# Balancing_FETs.net
KiCad netlist of a schematic drawn in Altium Designer
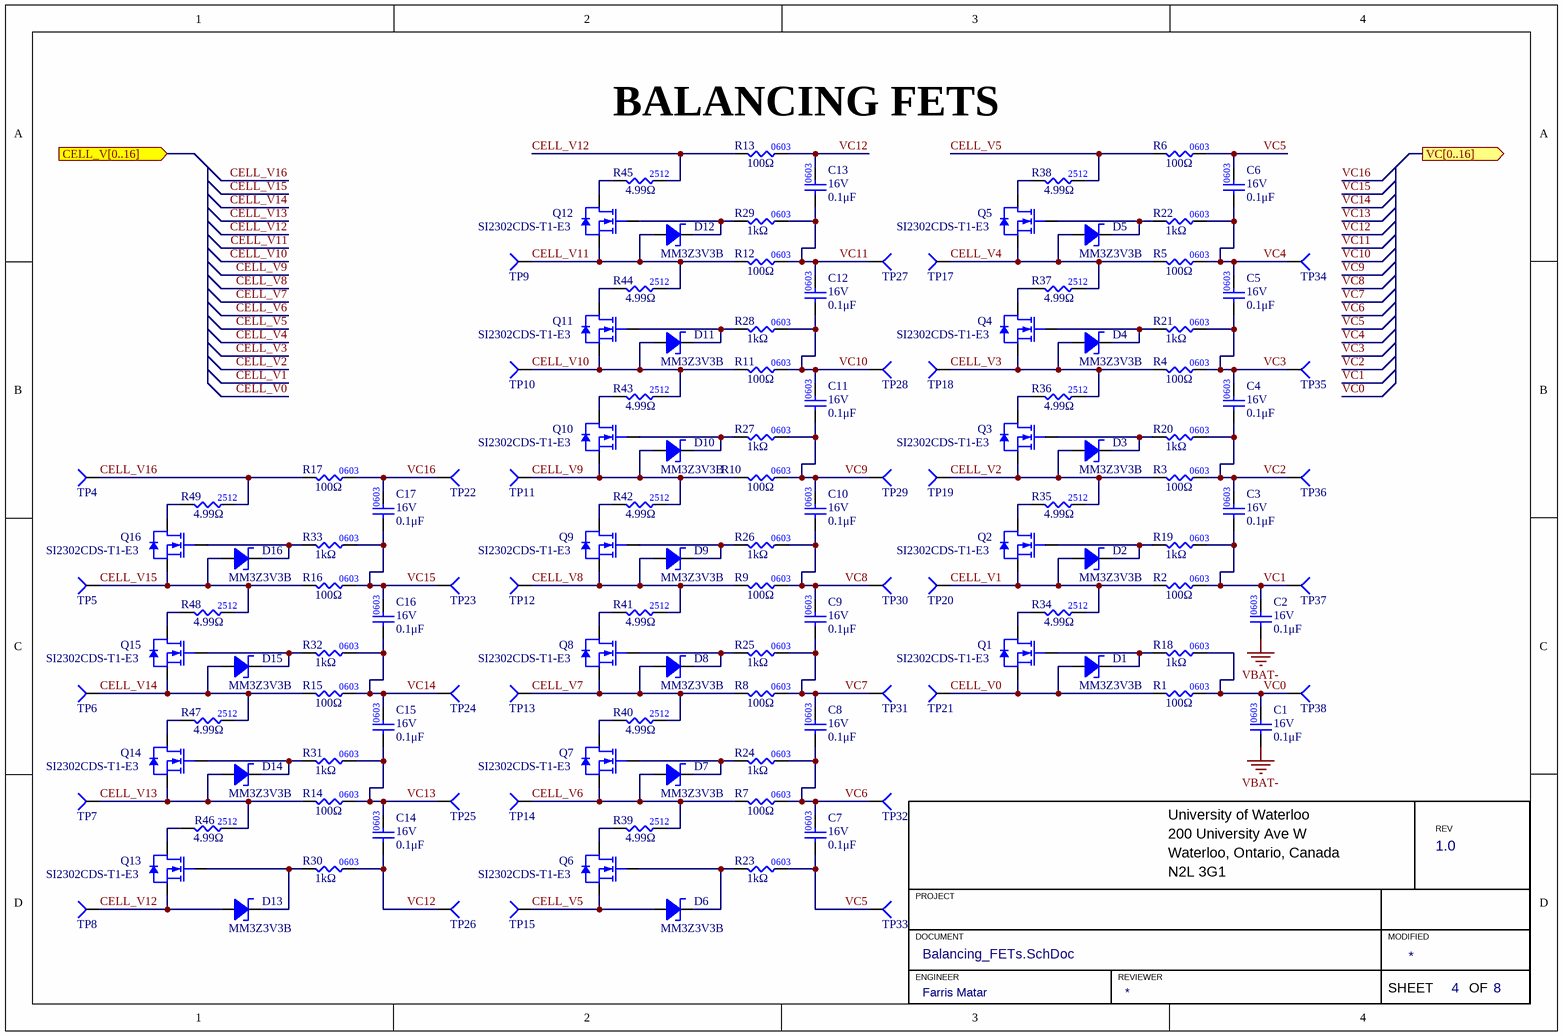
[diagram p0: Balancing_FETs.SchDoc]

(export (version "E")
  (design (tool "Eeschema 10.0.6"))
  (components
    (comp (ref "C1")
      (value "0.1μF")
      (footprint "CAP0603")
      (description "CAP CER 0.1UF 16V X7R 0603")
      (fields (field (name "VOLTAGE RATING") "16V") (field (name "Comment") "CAP_0.1uF_16V_0603"))
      (libsource (lib "Personal_Schematic_Library_2022") (part "CAP_0.1uF_16V_0603"))
    )
    (comp (ref "C2")
      (value "0.1μF")
      (footprint "CAP0603")
      (description "CAP CER 0.1UF 16V X7R 0603")
      (fields (field (name "VOLTAGE RATING") "16V") (field (name "Comment") "CAP_0.1uF_16V_0603"))
      (libsource (lib "Personal_Schematic_Library_2022") (part "CAP_0.1uF_16V_0603"))
    )
    (comp (ref "C3")
      (value "0.1μF")
      (footprint "CAP0603")
      (description "CAP CER 0.1UF 16V X7R 0603")
      (fields (field (name "VOLTAGE RATING") "16V") (field (name "Comment") "CAP_0.1uF_16V_0603"))
      (libsource (lib "Personal_Schematic_Library_2022") (part "CAP_0.1uF_16V_0603"))
    )
    (comp (ref "C4")
      (value "0.1μF")
      (footprint "CAP0603")
      (description "CAP CER 0.1UF 16V X7R 0603")
      (fields (field (name "VOLTAGE RATING") "16V") (field (name "Comment") "CAP_0.1uF_16V_0603"))
      (libsource (lib "Personal_Schematic_Library_2022") (part "CAP_0.1uF_16V_0603"))
    )
    (comp (ref "C5")
      (value "0.1μF")
      (footprint "CAP0603")
      (description "CAP CER 0.1UF 16V X7R 0603")
      (fields (field (name "VOLTAGE RATING") "16V") (field (name "Comment") "CAP_0.1uF_16V_0603"))
      (libsource (lib "Personal_Schematic_Library_2022") (part "CAP_0.1uF_16V_0603"))
    )
    (comp (ref "C6")
      (value "0.1μF")
      (footprint "CAP0603")
      (description "CAP CER 0.1UF 16V X7R 0603")
      (fields (field (name "VOLTAGE RATING") "16V") (field (name "Comment") "CAP_0.1uF_16V_0603"))
      (libsource (lib "Personal_Schematic_Library_2022") (part "CAP_0.1uF_16V_0603"))
    )
    (comp (ref "C7")
      (value "0.1μF")
      (footprint "CAP0603")
      (description "CAP CER 0.1UF 16V X7R 0603")
      (fields (field (name "VOLTAGE RATING") "16V") (field (name "Comment") "CAP_0.1uF_16V_0603"))
      (libsource (lib "Personal_Schematic_Library_2022") (part "CAP_0.1uF_16V_0603"))
    )
    (comp (ref "C8")
      (value "0.1μF")
      (footprint "CAP0603")
      (description "CAP CER 0.1UF 16V X7R 0603")
      (fields (field (name "VOLTAGE RATING") "16V") (field (name "Comment") "CAP_0.1uF_16V_0603"))
      (libsource (lib "Personal_Schematic_Library_2022") (part "CAP_0.1uF_16V_0603"))
    )
    (comp (ref "C9")
      (value "0.1μF")
      (footprint "CAP0603")
      (description "CAP CER 0.1UF 16V X7R 0603")
      (fields (field (name "VOLTAGE RATING") "16V") (field (name "Comment") "CAP_0.1uF_16V_0603"))
      (libsource (lib "Personal_Schematic_Library_2022") (part "CAP_0.1uF_16V_0603"))
    )
    (comp (ref "C10")
      (value "0.1μF")
      (footprint "CAP0603")
      (description "CAP CER 0.1UF 16V X7R 0603")
      (fields (field (name "VOLTAGE RATING") "16V") (field (name "Comment") "CAP_0.1uF_16V_0603"))
      (libsource (lib "Personal_Schematic_Library_2022") (part "CAP_0.1uF_16V_0603"))
    )
    (comp (ref "C11")
      (value "0.1μF")
      (footprint "CAP0603")
      (description "CAP CER 0.1UF 16V X7R 0603")
      (fields (field (name "VOLTAGE RATING") "16V") (field (name "Comment") "CAP_0.1uF_16V_0603"))
      (libsource (lib "Personal_Schematic_Library_2022") (part "CAP_0.1uF_16V_0603"))
    )
    (comp (ref "C12")
      (value "0.1μF")
      (footprint "CAP0603")
      (description "CAP CER 0.1UF 16V X7R 0603")
      (fields (field (name "VOLTAGE RATING") "16V") (field (name "Comment") "CAP_0.1uF_16V_0603"))
      (libsource (lib "Personal_Schematic_Library_2022") (part "CAP_0.1uF_16V_0603"))
    )
    (comp (ref "C13")
      (value "0.1μF")
      (footprint "CAP0603")
      (description "CAP CER 0.1UF 16V X7R 0603")
      (fields (field (name "VOLTAGE RATING") "16V") (field (name "Comment") "CAP_0.1uF_16V_0603"))
      (libsource (lib "Personal_Schematic_Library_2022") (part "CAP_0.1uF_16V_0603"))
    )
    (comp (ref "C14")
      (value "0.1μF")
      (footprint "CAP0603")
      (description "CAP CER 0.1UF 16V X7R 0603")
      (fields (field (name "VOLTAGE RATING") "16V") (field (name "Comment") "CAP_0.1uF_16V_0603"))
      (libsource (lib "Personal_Schematic_Library_2022") (part "CAP_0.1uF_16V_0603"))
    )
    (comp (ref "C15")
      (value "0.1μF")
      (footprint "CAP0603")
      (description "CAP CER 0.1UF 16V X7R 0603")
      (fields (field (name "VOLTAGE RATING") "16V") (field (name "Comment") "CAP_0.1uF_16V_0603"))
      (libsource (lib "Personal_Schematic_Library_2022") (part "CAP_0.1uF_16V_0603"))
    )
    (comp (ref "C16")
      (value "0.1μF")
      (footprint "CAP0603")
      (description "CAP CER 0.1UF 16V X7R 0603")
      (fields (field (name "VOLTAGE RATING") "16V") (field (name "Comment") "CAP_0.1uF_16V_0603"))
      (libsource (lib "Personal_Schematic_Library_2022") (part "CAP_0.1uF_16V_0603"))
    )
    (comp (ref "C17")
      (value "0.1μF")
      (footprint "CAP0603")
      (description "CAP CER 0.1UF 16V X7R 0603")
      (fields (field (name "VOLTAGE RATING") "16V") (field (name "Comment") "CAP_0.1uF_16V_0603"))
      (libsource (lib "Personal_Schematic_Library_2022") (part "CAP_0.1uF_16V_0603"))
    )
    (comp (ref "D1")
      (value "DIO_ZENER_3V3")
      (footprint "DIO_ZENER_3V3")
      (description "DIODE ZENER 3.3V 200mW SOD323F")
      (fields (field (name "MANUFACTURER PART NUMBER 1") "MM3Z3V3B"))
      (libsource (lib "Personal_Schematic_Library_2022") (part "DIO_ZENER_3V3"))
    )
    (comp (ref "D2")
      (value "DIO_ZENER_3V3")
      (footprint "DIO_ZENER_3V3")
      (description "DIODE ZENER 3.3V 200mW SOD323F")
      (fields (field (name "MANUFACTURER PART NUMBER 1") "MM3Z3V3B"))
      (libsource (lib "Personal_Schematic_Library_2022") (part "DIO_ZENER_3V3"))
    )
    (comp (ref "D3")
      (value "DIO_ZENER_3V3")
      (footprint "DIO_ZENER_3V3")
      (description "DIODE ZENER 3.3V 200mW SOD323F")
      (fields (field (name "MANUFACTURER PART NUMBER 1") "MM3Z3V3B"))
      (libsource (lib "Personal_Schematic_Library_2022") (part "DIO_ZENER_3V3"))
    )
    (comp (ref "D4")
      (value "DIO_ZENER_3V3")
      (footprint "DIO_ZENER_3V3")
      (description "DIODE ZENER 3.3V 200mW SOD323F")
      (fields (field (name "MANUFACTURER PART NUMBER 1") "MM3Z3V3B"))
      (libsource (lib "Personal_Schematic_Library_2022") (part "DIO_ZENER_3V3"))
    )
    (comp (ref "D5")
      (value "DIO_ZENER_3V3")
      (footprint "DIO_ZENER_3V3")
      (description "DIODE ZENER 3.3V 200mW SOD323F")
      (fields (field (name "MANUFACTURER PART NUMBER 1") "MM3Z3V3B"))
      (libsource (lib "Personal_Schematic_Library_2022") (part "DIO_ZENER_3V3"))
    )
    (comp (ref "D6")
      (value "DIO_ZENER_3V3")
      (footprint "DIO_ZENER_3V3")
      (description "DIODE ZENER 3.3V 200mW SOD323F")
      (fields (field (name "MANUFACTURER PART NUMBER 1") "MM3Z3V3B"))
      (libsource (lib "Personal_Schematic_Library_2022") (part "DIO_ZENER_3V3"))
    )
    (comp (ref "D7")
      (value "DIO_ZENER_3V3")
      (footprint "DIO_ZENER_3V3")
      (description "DIODE ZENER 3.3V 200mW SOD323F")
      (fields (field (name "MANUFACTURER PART NUMBER 1") "MM3Z3V3B"))
      (libsource (lib "Personal_Schematic_Library_2022") (part "DIO_ZENER_3V3"))
    )
    (comp (ref "D8")
      (value "DIO_ZENER_3V3")
      (footprint "DIO_ZENER_3V3")
      (description "DIODE ZENER 3.3V 200mW SOD323F")
      (fields (field (name "MANUFACTURER PART NUMBER 1") "MM3Z3V3B"))
      (libsource (lib "Personal_Schematic_Library_2022") (part "DIO_ZENER_3V3"))
    )
    (comp (ref "D9")
      (value "DIO_ZENER_3V3")
      (footprint "DIO_ZENER_3V3")
      (description "DIODE ZENER 3.3V 200mW SOD323F")
      (fields (field (name "MANUFACTURER PART NUMBER 1") "MM3Z3V3B"))
      (libsource (lib "Personal_Schematic_Library_2022") (part "DIO_ZENER_3V3"))
    )
    (comp (ref "D10")
      (value "DIO_ZENER_3V3")
      (footprint "DIO_ZENER_3V3")
      (description "DIODE ZENER 3.3V 200mW SOD323F")
      (fields (field (name "MANUFACTURER PART NUMBER 1") "MM3Z3V3B"))
      (libsource (lib "Personal_Schematic_Library_2022") (part "DIO_ZENER_3V3"))
    )
    (comp (ref "D11")
      (value "DIO_ZENER_3V3")
      (footprint "DIO_ZENER_3V3")
      (description "DIODE ZENER 3.3V 200mW SOD323F")
      (fields (field (name "MANUFACTURER PART NUMBER 1") "MM3Z3V3B"))
      (libsource (lib "Personal_Schematic_Library_2022") (part "DIO_ZENER_3V3"))
    )
    (comp (ref "D12")
      (value "DIO_ZENER_3V3")
      (footprint "DIO_ZENER_3V3")
      (description "DIODE ZENER 3.3V 200mW SOD323F")
      (fields (field (name "MANUFACTURER PART NUMBER 1") "MM3Z3V3B"))
      (libsource (lib "Personal_Schematic_Library_2022") (part "DIO_ZENER_3V3"))
    )
    (comp (ref "D13")
      (value "DIO_ZENER_3V3")
      (footprint "DIO_ZENER_3V3")
      (description "DIODE ZENER 3.3V 200mW SOD323F")
      (fields (field (name "MANUFACTURER PART NUMBER 1") "MM3Z3V3B"))
      (libsource (lib "Personal_Schematic_Library_2022") (part "DIO_ZENER_3V3"))
    )
    (comp (ref "D14")
      (value "DIO_ZENER_3V3")
      (footprint "DIO_ZENER_3V3")
      (description "DIODE ZENER 3.3V 200mW SOD323F")
      (fields (field (name "MANUFACTURER PART NUMBER 1") "MM3Z3V3B"))
      (libsource (lib "Personal_Schematic_Library_2022") (part "DIO_ZENER_3V3"))
    )
    (comp (ref "D15")
      (value "DIO_ZENER_3V3")
      (footprint "DIO_ZENER_3V3")
      (description "DIODE ZENER 3.3V 200mW SOD323F")
      (fields (field (name "MANUFACTURER PART NUMBER 1") "MM3Z3V3B"))
      (libsource (lib "Personal_Schematic_Library_2022") (part "DIO_ZENER_3V3"))
    )
    (comp (ref "D16")
      (value "DIO_ZENER_3V3")
      (footprint "DIO_ZENER_3V3")
      (description "DIODE ZENER 3.3V 200mW SOD323F")
      (fields (field (name "MANUFACTURER PART NUMBER 1") "MM3Z3V3B"))
      (libsource (lib "Personal_Schematic_Library_2022") (part "DIO_ZENER_3V3"))
    )
    (comp (ref "Q1")
      (value "NMOS_20V_6A")
      (footprint "SOT23-3")
      (description "MOSFET N-CH 20V 2.6A SOT23-3")
      (fields (field (name "MANUFACTURER PART NUMBER 1") "SI2302CDS-T1-E3"))
      (libsource (lib "Personal_Schematic_Library_2022") (part "NMOS_20V_2.6A"))
    )
    (comp (ref "Q2")
      (value "NMOS_20V_6A")
      (footprint "SOT23-3")
      (description "MOSFET N-CH 20V 2.6A SOT23-3")
      (fields (field (name "MANUFACTURER PART NUMBER 1") "SI2302CDS-T1-E3"))
      (libsource (lib "Personal_Schematic_Library_2022") (part "NMOS_20V_2.6A"))
    )
    (comp (ref "Q3")
      (value "NMOS_20V_6A")
      (footprint "SOT23-3")
      (description "MOSFET N-CH 20V 2.6A SOT23-3")
      (fields (field (name "MANUFACTURER PART NUMBER 1") "SI2302CDS-T1-E3"))
      (libsource (lib "Personal_Schematic_Library_2022") (part "NMOS_20V_2.6A"))
    )
    (comp (ref "Q4")
      (value "NMOS_20V_6A")
      (footprint "SOT23-3")
      (description "MOSFET N-CH 20V 2.6A SOT23-3")
      (fields (field (name "MANUFACTURER PART NUMBER 1") "SI2302CDS-T1-E3"))
      (libsource (lib "Personal_Schematic_Library_2022") (part "NMOS_20V_2.6A"))
    )
    (comp (ref "Q5")
      (value "NMOS_20V_6A")
      (footprint "SOT23-3")
      (description "MOSFET N-CH 20V 2.6A SOT23-3")
      (fields (field (name "MANUFACTURER PART NUMBER 1") "SI2302CDS-T1-E3"))
      (libsource (lib "Personal_Schematic_Library_2022") (part "NMOS_20V_2.6A"))
    )
    (comp (ref "Q6")
      (value "NMOS_20V_6A")
      (footprint "SOT23-3")
      (description "MOSFET N-CH 20V 2.6A SOT23-3")
      (fields (field (name "MANUFACTURER PART NUMBER 1") "SI2302CDS-T1-E3"))
      (libsource (lib "Personal_Schematic_Library_2022") (part "NMOS_20V_2.6A"))
    )
    (comp (ref "Q7")
      (value "NMOS_20V_6A")
      (footprint "SOT23-3")
      (description "MOSFET N-CH 20V 2.6A SOT23-3")
      (fields (field (name "MANUFACTURER PART NUMBER 1") "SI2302CDS-T1-E3"))
      (libsource (lib "Personal_Schematic_Library_2022") (part "NMOS_20V_2.6A"))
    )
    (comp (ref "Q8")
      (value "NMOS_20V_6A")
      (footprint "SOT23-3")
      (description "MOSFET N-CH 20V 2.6A SOT23-3")
      (fields (field (name "MANUFACTURER PART NUMBER 1") "SI2302CDS-T1-E3"))
      (libsource (lib "Personal_Schematic_Library_2022") (part "NMOS_20V_2.6A"))
    )
    (comp (ref "Q9")
      (value "NMOS_20V_6A")
      (footprint "SOT23-3")
      (description "MOSFET N-CH 20V 2.6A SOT23-3")
      (fields (field (name "MANUFACTURER PART NUMBER 1") "SI2302CDS-T1-E3"))
      (libsource (lib "Personal_Schematic_Library_2022") (part "NMOS_20V_2.6A"))
    )
    (comp (ref "Q10")
      (value "NMOS_20V_6A")
      (footprint "SOT23-3")
      (description "MOSFET N-CH 20V 2.6A SOT23-3")
      (fields (field (name "MANUFACTURER PART NUMBER 1") "SI2302CDS-T1-E3"))
      (libsource (lib "Personal_Schematic_Library_2022") (part "NMOS_20V_2.6A"))
    )
    (comp (ref "Q11")
      (value "NMOS_20V_6A")
      (footprint "SOT23-3")
      (description "MOSFET N-CH 20V 2.6A SOT23-3")
      (fields (field (name "MANUFACTURER PART NUMBER 1") "SI2302CDS-T1-E3"))
      (libsource (lib "Personal_Schematic_Library_2022") (part "NMOS_20V_2.6A"))
    )
    (comp (ref "Q12")
      (value "NMOS_20V_6A")
      (footprint "SOT23-3")
      (description "MOSFET N-CH 20V 2.6A SOT23-3")
      (fields (field (name "MANUFACTURER PART NUMBER 1") "SI2302CDS-T1-E3"))
      (libsource (lib "Personal_Schematic_Library_2022") (part "NMOS_20V_2.6A"))
    )
    (comp (ref "Q13")
      (value "NMOS_20V_6A")
      (footprint "SOT23-3")
      (description "MOSFET N-CH 20V 2.6A SOT23-3")
      (fields (field (name "MANUFACTURER PART NUMBER 1") "SI2302CDS-T1-E3"))
      (libsource (lib "Personal_Schematic_Library_2022") (part "NMOS_20V_2.6A"))
    )
    (comp (ref "Q14")
      (value "NMOS_20V_6A")
      (footprint "SOT23-3")
      (description "MOSFET N-CH 20V 2.6A SOT23-3")
      (fields (field (name "MANUFACTURER PART NUMBER 1") "SI2302CDS-T1-E3"))
      (libsource (lib "Personal_Schematic_Library_2022") (part "NMOS_20V_2.6A"))
    )
    (comp (ref "Q15")
      (value "NMOS_20V_6A")
      (footprint "SOT23-3")
      (description "MOSFET N-CH 20V 2.6A SOT23-3")
      (fields (field (name "MANUFACTURER PART NUMBER 1") "SI2302CDS-T1-E3"))
      (libsource (lib "Personal_Schematic_Library_2022") (part "NMOS_20V_2.6A"))
    )
    (comp (ref "Q16")
      (value "NMOS_20V_6A")
      (footprint "SOT23-3")
      (description "MOSFET N-CH 20V 2.6A SOT23-3")
      (fields (field (name "MANUFACTURER PART NUMBER 1") "SI2302CDS-T1-E3"))
      (libsource (lib "Personal_Schematic_Library_2022") (part "NMOS_20V_2.6A"))
    )
    (comp (ref "R1")
      (value "100Ω")
      (footprint "RES0603")
      (description "RES 100 OHM 1% 1/10W 0603")
      (fields (field (name "Comment") "RES_100Ω_0603_1%"))
      (libsource (lib "Personal_Schematic_Library_2022") (part "RES_100Ω_0603_1%"))
    )
    (comp (ref "R2")
      (value "100Ω")
      (footprint "RES0603")
      (description "RES 100 OHM 1% 1/10W 0603")
      (fields (field (name "Comment") "RES_100Ω_0603_1%"))
      (libsource (lib "Personal_Schematic_Library_2022") (part "RES_100Ω_0603_1%"))
    )
    (comp (ref "R3")
      (value "100Ω")
      (footprint "RES0603")
      (description "RES 100 OHM 1% 1/10W 0603")
      (fields (field (name "Comment") "RES_100Ω_0603_1%"))
      (libsource (lib "Personal_Schematic_Library_2022") (part "RES_100Ω_0603_1%"))
    )
    (comp (ref "R4")
      (value "100Ω")
      (footprint "RES0603")
      (description "RES 100 OHM 1% 1/10W 0603")
      (fields (field (name "Comment") "RES_100Ω_0603_1%"))
      (libsource (lib "Personal_Schematic_Library_2022") (part "RES_100Ω_0603_1%"))
    )
    (comp (ref "R5")
      (value "100Ω")
      (footprint "RES0603")
      (description "RES 100 OHM 1% 1/10W 0603")
      (fields (field (name "Comment") "RES_100Ω_0603_1%"))
      (libsource (lib "Personal_Schematic_Library_2022") (part "RES_100Ω_0603_1%"))
    )
    (comp (ref "R6")
      (value "100Ω")
      (footprint "RES0603")
      (description "RES 100 OHM 1% 1/10W 0603")
      (fields (field (name "Comment") "RES_100Ω_0603_1%"))
      (libsource (lib "Personal_Schematic_Library_2022") (part "RES_100Ω_0603_1%"))
    )
    (comp (ref "R7")
      (value "100Ω")
      (footprint "RES0603")
      (description "RES 100 OHM 1% 1/10W 0603")
      (fields (field (name "Comment") "RES_100Ω_0603_1%"))
      (libsource (lib "Personal_Schematic_Library_2022") (part "RES_100Ω_0603_1%"))
    )
    (comp (ref "R8")
      (value "100Ω")
      (footprint "RES0603")
      (description "RES 100 OHM 1% 1/10W 0603")
      (fields (field (name "Comment") "RES_100Ω_0603_1%"))
      (libsource (lib "Personal_Schematic_Library_2022") (part "RES_100Ω_0603_1%"))
    )
    (comp (ref "R9")
      (value "100Ω")
      (footprint "RES0603")
      (description "RES 100 OHM 1% 1/10W 0603")
      (fields (field (name "Comment") "RES_100Ω_0603_1%"))
      (libsource (lib "Personal_Schematic_Library_2022") (part "RES_100Ω_0603_1%"))
    )
    (comp (ref "R10")
      (value "100Ω")
      (footprint "RES0603")
      (description "RES 100 OHM 1% 1/10W 0603")
      (fields (field (name "Comment") "RES_100Ω_0603_1%"))
      (libsource (lib "Personal_Schematic_Library_2022") (part "RES_100Ω_0603_1%"))
    )
    (comp (ref "R11")
      (value "100Ω")
      (footprint "RES0603")
      (description "RES 100 OHM 1% 1/10W 0603")
      (fields (field (name "Comment") "RES_100Ω_0603_1%"))
      (libsource (lib "Personal_Schematic_Library_2022") (part "RES_100Ω_0603_1%"))
    )
    (comp (ref "R12")
      (value "100Ω")
      (footprint "RES0603")
      (description "RES 100 OHM 1% 1/10W 0603")
      (fields (field (name "Comment") "RES_100Ω_0603_1%"))
      (libsource (lib "Personal_Schematic_Library_2022") (part "RES_100Ω_0603_1%"))
    )
    (comp (ref "R13")
      (value "100Ω")
      (footprint "RES0603")
      (description "RES 100 OHM 1% 1/10W 0603")
      (fields (field (name "Comment") "RES_100Ω_0603_1%"))
      (libsource (lib "Personal_Schematic_Library_2022") (part "RES_100Ω_0603_1%"))
    )
    (comp (ref "R14")
      (value "100Ω")
      (footprint "RES0603")
      (description "RES 100 OHM 1% 1/10W 0603")
      (fields (field (name "Comment") "RES_100Ω_0603_1%"))
      (libsource (lib "Personal_Schematic_Library_2022") (part "RES_100Ω_0603_1%"))
    )
    (comp (ref "R15")
      (value "100Ω")
      (footprint "RES0603")
      (description "RES 100 OHM 1% 1/10W 0603")
      (fields (field (name "Comment") "RES_100Ω_0603_1%"))
      (libsource (lib "Personal_Schematic_Library_2022") (part "RES_100Ω_0603_1%"))
    )
    (comp (ref "R16")
      (value "100Ω")
      (footprint "RES0603")
      (description "RES 100 OHM 1% 1/10W 0603")
      (fields (field (name "Comment") "RES_100Ω_0603_1%"))
      (libsource (lib "Personal_Schematic_Library_2022") (part "RES_100Ω_0603_1%"))
    )
    (comp (ref "R17")
      (value "100Ω")
      (footprint "RES0603")
      (description "RES 100 OHM 1% 1/10W 0603")
      (fields (field (name "Comment") "RES_100Ω_0603_1%"))
      (libsource (lib "Personal_Schematic_Library_2022") (part "RES_100Ω_0603_1%"))
    )
    (comp (ref "R18")
      (value "1kΩ")
      (footprint "RES0603")
      (description "RES 1K OHM 1% 1/8W 0603")
      (fields (field (name "Comment") "RES_1kΩ_0603_1%"))
      (libsource (lib "Personal_Schematic_Library_2022") (part "RES_1kΩ_0603_1%"))
    )
    (comp (ref "R19")
      (value "1kΩ")
      (footprint "RES0603")
      (description "RES 1K OHM 1% 1/8W 0603")
      (fields (field (name "Comment") "RES_1kΩ_0603_1%"))
      (libsource (lib "Personal_Schematic_Library_2022") (part "RES_1kΩ_0603_1%"))
    )
    (comp (ref "R20")
      (value "1kΩ")
      (footprint "RES0603")
      (description "RES 1K OHM 1% 1/8W 0603")
      (fields (field (name "Comment") "RES_1kΩ_0603_1%"))
      (libsource (lib "Personal_Schematic_Library_2022") (part "RES_1kΩ_0603_1%"))
    )
    (comp (ref "R21")
      (value "1kΩ")
      (footprint "RES0603")
      (description "RES 1K OHM 1% 1/8W 0603")
      (fields (field (name "Comment") "RES_1kΩ_0603_1%"))
      (libsource (lib "Personal_Schematic_Library_2022") (part "RES_1kΩ_0603_1%"))
    )
    (comp (ref "R22")
      (value "1kΩ")
      (footprint "RES0603")
      (description "RES 1K OHM 1% 1/8W 0603")
      (fields (field (name "Comment") "RES_1kΩ_0603_1%"))
      (libsource (lib "Personal_Schematic_Library_2022") (part "RES_1kΩ_0603_1%"))
    )
    (comp (ref "R23")
      (value "1kΩ")
      (footprint "RES0603")
      (description "RES 1K OHM 1% 1/8W 0603")
      (fields (field (name "Comment") "RES_1kΩ_0603_1%"))
      (libsource (lib "Personal_Schematic_Library_2022") (part "RES_1kΩ_0603_1%"))
    )
    (comp (ref "R24")
      (value "1kΩ")
      (footprint "RES0603")
      (description "RES 1K OHM 1% 1/8W 0603")
      (fields (field (name "Comment") "RES_1kΩ_0603_1%"))
      (libsource (lib "Personal_Schematic_Library_2022") (part "RES_1kΩ_0603_1%"))
    )
    (comp (ref "R25")
      (value "1kΩ")
      (footprint "RES0603")
      (description "RES 1K OHM 1% 1/8W 0603")
      (fields (field (name "Comment") "RES_1kΩ_0603_1%"))
      (libsource (lib "Personal_Schematic_Library_2022") (part "RES_1kΩ_0603_1%"))
    )
    (comp (ref "R26")
      (value "1kΩ")
      (footprint "RES0603")
      (description "RES 1K OHM 1% 1/8W 0603")
      (fields (field (name "Comment") "RES_1kΩ_0603_1%"))
      (libsource (lib "Personal_Schematic_Library_2022") (part "RES_1kΩ_0603_1%"))
    )
    (comp (ref "R27")
      (value "1kΩ")
      (footprint "RES0603")
      (description "RES 1K OHM 1% 1/8W 0603")
      (fields (field (name "Comment") "RES_1kΩ_0603_1%"))
      (libsource (lib "Personal_Schematic_Library_2022") (part "RES_1kΩ_0603_1%"))
    )
    (comp (ref "R28")
      (value "1kΩ")
      (footprint "RES0603")
      (description "RES 1K OHM 1% 1/8W 0603")
      (fields (field (name "Comment") "RES_1kΩ_0603_1%"))
      (libsource (lib "Personal_Schematic_Library_2022") (part "RES_1kΩ_0603_1%"))
    )
    (comp (ref "R29")
      (value "1kΩ")
      (footprint "RES0603")
      (description "RES 1K OHM 1% 1/8W 0603")
      (fields (field (name "Comment") "RES_1kΩ_0603_1%"))
      (libsource (lib "Personal_Schematic_Library_2022") (part "RES_1kΩ_0603_1%"))
    )
    (comp (ref "R30")
      (value "1kΩ")
      (footprint "RES0603")
      (description "RES 1K OHM 1% 1/8W 0603")
      (fields (field (name "Comment") "RES_1kΩ_0603_1%"))
      (libsource (lib "Personal_Schematic_Library_2022") (part "RES_1kΩ_0603_1%"))
    )
    (comp (ref "R31")
      (value "1kΩ")
      (footprint "RES0603")
      (description "RES 1K OHM 1% 1/8W 0603")
      (fields (field (name "Comment") "RES_1kΩ_0603_1%"))
      (libsource (lib "Personal_Schematic_Library_2022") (part "RES_1kΩ_0603_1%"))
    )
    (comp (ref "R32")
      (value "1kΩ")
      (footprint "RES0603")
      (description "RES 1K OHM 1% 1/8W 0603")
      (fields (field (name "Comment") "RES_1kΩ_0603_1%"))
      (libsource (lib "Personal_Schematic_Library_2022") (part "RES_1kΩ_0603_1%"))
    )
    (comp (ref "R33")
      (value "1kΩ")
      (footprint "RES0603")
      (description "RES 1K OHM 1% 1/8W 0603")
      (fields (field (name "Comment") "RES_1kΩ_0603_1%"))
      (libsource (lib "Personal_Schematic_Library_2022") (part "RES_1kΩ_0603_1%"))
    )
    (comp (ref "R34")
      (value "4.99Ω")
      (footprint "RES2512")
      (description "RES 4.99 OHM 1% 2W 2512")
      (fields (field (name "Comment") "RES_4.99Ω_2512_1%"))
      (libsource (lib "Personal_Schematic_Library_2022") (part "RES_4.99Ω_2512_1%"))
    )
    (comp (ref "R35")
      (value "4.99Ω")
      (footprint "RES2512")
      (description "RES 4.99 OHM 1% 2W 2512")
      (fields (field (name "Comment") "RES_4.99Ω_2512_1%"))
      (libsource (lib "Personal_Schematic_Library_2022") (part "RES_4.99Ω_2512_1%"))
    )
    (comp (ref "R36")
      (value "4.99Ω")
      (footprint "RES2512")
      (description "RES 4.99 OHM 1% 2W 2512")
      (fields (field (name "Comment") "RES_4.99Ω_2512_1%"))
      (libsource (lib "Personal_Schematic_Library_2022") (part "RES_4.99Ω_2512_1%"))
    )
    (comp (ref "R37")
      (value "4.99Ω")
      (footprint "RES2512")
      (description "RES 4.99 OHM 1% 2W 2512")
      (fields (field (name "Comment") "RES_4.99Ω_2512_1%"))
      (libsource (lib "Personal_Schematic_Library_2022") (part "RES_4.99Ω_2512_1%"))
    )
    (comp (ref "R38")
      (value "4.99Ω")
      (footprint "RES2512")
      (description "RES 4.99 OHM 1% 2W 2512")
      (fields (field (name "Comment") "RES_4.99Ω_2512_1%"))
      (libsource (lib "Personal_Schematic_Library_2022") (part "RES_4.99Ω_2512_1%"))
    )
    (comp (ref "R39")
      (value "4.99Ω")
      (footprint "RES2512")
      (description "RES 4.99 OHM 1% 2W 2512")
      (fields (field (name "Comment") "RES_4.99Ω_2512_1%"))
      (libsource (lib "Personal_Schematic_Library_2022") (part "RES_4.99Ω_2512_1%"))
    )
    (comp (ref "R40")
      (value "4.99Ω")
      (footprint "RES2512")
      (description "RES 4.99 OHM 1% 2W 2512")
      (fields (field (name "Comment") "RES_4.99Ω_2512_1%"))
      (libsource (lib "Personal_Schematic_Library_2022") (part "RES_4.99Ω_2512_1%"))
    )
    (comp (ref "R41")
      (value "4.99Ω")
      (footprint "RES2512")
      (description "RES 4.99 OHM 1% 2W 2512")
      (fields (field (name "Comment") "RES_4.99Ω_2512_1%"))
      (libsource (lib "Personal_Schematic_Library_2022") (part "RES_4.99Ω_2512_1%"))
    )
    (comp (ref "R42")
      (value "4.99Ω")
      (footprint "RES2512")
      (description "RES 4.99 OHM 1% 2W 2512")
      (fields (field (name "Comment") "RES_4.99Ω_2512_1%"))
      (libsource (lib "Personal_Schematic_Library_2022") (part "RES_4.99Ω_2512_1%"))
    )
    (comp (ref "R43")
      (value "4.99Ω")
      (footprint "RES2512")
      (description "RES 4.99 OHM 1% 2W 2512")
      (fields (field (name "Comment") "RES_4.99Ω_2512_1%"))
      (libsource (lib "Personal_Schematic_Library_2022") (part "RES_4.99Ω_2512_1%"))
    )
    (comp (ref "R44")
      (value "4.99Ω")
      (footprint "RES2512")
      (description "RES 4.99 OHM 1% 2W 2512")
      (fields (field (name "Comment") "RES_4.99Ω_2512_1%"))
      (libsource (lib "Personal_Schematic_Library_2022") (part "RES_4.99Ω_2512_1%"))
    )
    (comp (ref "R45")
      (value "4.99Ω")
      (footprint "RES2512")
      (description "RES 4.99 OHM 1% 2W 2512")
      (fields (field (name "Comment") "RES_4.99Ω_2512_1%"))
      (libsource (lib "Personal_Schematic_Library_2022") (part "RES_4.99Ω_2512_1%"))
    )
    (comp (ref "R46")
      (value "4.99Ω")
      (footprint "RES2512")
      (description "RES 4.99 OHM 1% 2W 2512")
      (fields (field (name "Comment") "RES_4.99Ω_2512_1%"))
      (libsource (lib "Personal_Schematic_Library_2022") (part "RES_4.99Ω_2512_1%"))
    )
    (comp (ref "R47")
      (value "4.99Ω")
      (footprint "RES2512")
      (description "RES 4.99 OHM 1% 2W 2512")
      (fields (field (name "Comment") "RES_4.99Ω_2512_1%"))
      (libsource (lib "Personal_Schematic_Library_2022") (part "RES_4.99Ω_2512_1%"))
    )
    (comp (ref "R48")
      (value "4.99Ω")
      (footprint "RES2512")
      (description "RES 4.99 OHM 1% 2W 2512")
      (fields (field (name "Comment") "RES_4.99Ω_2512_1%"))
      (libsource (lib "Personal_Schematic_Library_2022") (part "RES_4.99Ω_2512_1%"))
    )
    (comp (ref "R49")
      (value "4.99Ω")
      (footprint "RES2512")
      (description "RES 4.99 OHM 1% 2W 2512")
      (fields (field (name "Comment") "RES_4.99Ω_2512_1%"))
      (libsource (lib "Personal_Schematic_Library_2022") (part "RES_4.99Ω_2512_1%"))
    )
    (comp (ref "TP4")
      (value "TESTPOINT_1MM_SQUARE")
      (footprint "TESTPOINT_SQUARE_1MM")
      (description "TESTPOINT 1MM SQUARE")
      (libsource (lib "Personal_Schematic_Library_2022") (part "TESTPOINT_1MM_SQUARE"))
    )
    (comp (ref "TP5")
      (value "TESTPOINT_1MM_SQUARE")
      (footprint "TESTPOINT_SQUARE_1MM")
      (description "TESTPOINT 1MM SQUARE")
      (libsource (lib "Personal_Schematic_Library_2022") (part "TESTPOINT_1MM_SQUARE"))
    )
    (comp (ref "TP6")
      (value "TESTPOINT_1MM_SQUARE")
      (footprint "TESTPOINT_SQUARE_1MM")
      (description "TESTPOINT 1MM SQUARE")
      (libsource (lib "Personal_Schematic_Library_2022") (part "TESTPOINT_1MM_SQUARE"))
    )
    (comp (ref "TP7")
      (value "TESTPOINT_1MM_SQUARE")
      (footprint "TESTPOINT_SQUARE_1MM")
      (description "TESTPOINT 1MM SQUARE")
      (libsource (lib "Personal_Schematic_Library_2022") (part "TESTPOINT_1MM_SQUARE"))
    )
    (comp (ref "TP8")
      (value "TESTPOINT_1MM_SQUARE")
      (footprint "TESTPOINT_SQUARE_1MM")
      (description "TESTPOINT 1MM SQUARE")
      (libsource (lib "Personal_Schematic_Library_2022") (part "TESTPOINT_1MM_SQUARE"))
    )
    (comp (ref "TP9")
      (value "TESTPOINT_1MM_SQUARE")
      (footprint "TESTPOINT_SQUARE_1MM")
      (description "TESTPOINT 1MM SQUARE")
      (libsource (lib "Personal_Schematic_Library_2022") (part "TESTPOINT_1MM_SQUARE"))
    )
    (comp (ref "TP10")
      (value "TESTPOINT_1MM_SQUARE")
      (footprint "TESTPOINT_SQUARE_1MM")
      (description "TESTPOINT 1MM SQUARE")
      (libsource (lib "Personal_Schematic_Library_2022") (part "TESTPOINT_1MM_SQUARE"))
    )
    (comp (ref "TP11")
      (value "TESTPOINT_1MM_SQUARE")
      (footprint "TESTPOINT_SQUARE_1MM")
      (description "TESTPOINT 1MM SQUARE")
      (libsource (lib "Personal_Schematic_Library_2022") (part "TESTPOINT_1MM_SQUARE"))
    )
    (comp (ref "TP12")
      (value "TESTPOINT_1MM_SQUARE")
      (footprint "TESTPOINT_SQUARE_1MM")
      (description "TESTPOINT 1MM SQUARE")
      (libsource (lib "Personal_Schematic_Library_2022") (part "TESTPOINT_1MM_SQUARE"))
    )
    (comp (ref "TP13")
      (value "TESTPOINT_1MM_SQUARE")
      (footprint "TESTPOINT_SQUARE_1MM")
      (description "TESTPOINT 1MM SQUARE")
      (libsource (lib "Personal_Schematic_Library_2022") (part "TESTPOINT_1MM_SQUARE"))
    )
    (comp (ref "TP14")
      (value "TESTPOINT_1MM_SQUARE")
      (footprint "TESTPOINT_SQUARE_1MM")
      (description "TESTPOINT 1MM SQUARE")
      (libsource (lib "Personal_Schematic_Library_2022") (part "TESTPOINT_1MM_SQUARE"))
    )
    (comp (ref "TP15")
      (value "TESTPOINT_1MM_SQUARE")
      (footprint "TESTPOINT_SQUARE_1MM")
      (description "TESTPOINT 1MM SQUARE")
      (libsource (lib "Personal_Schematic_Library_2022") (part "TESTPOINT_1MM_SQUARE"))
    )
    (comp (ref "TP17")
      (value "TESTPOINT_1MM_SQUARE")
      (footprint "TESTPOINT_SQUARE_1MM")
      (description "TESTPOINT 1MM SQUARE")
      (libsource (lib "Personal_Schematic_Library_2022") (part "TESTPOINT_1MM_SQUARE"))
    )
    (comp (ref "TP18")
      (value "TESTPOINT_1MM_SQUARE")
      (footprint "TESTPOINT_SQUARE_1MM")
      (description "TESTPOINT 1MM SQUARE")
      (libsource (lib "Personal_Schematic_Library_2022") (part "TESTPOINT_1MM_SQUARE"))
    )
    (comp (ref "TP19")
      (value "TESTPOINT_1MM_SQUARE")
      (footprint "TESTPOINT_SQUARE_1MM")
      (description "TESTPOINT 1MM SQUARE")
      (libsource (lib "Personal_Schematic_Library_2022") (part "TESTPOINT_1MM_SQUARE"))
    )
    (comp (ref "TP20")
      (value "TESTPOINT_1MM_SQUARE")
      (footprint "TESTPOINT_SQUARE_1MM")
      (description "TESTPOINT 1MM SQUARE")
      (libsource (lib "Personal_Schematic_Library_2022") (part "TESTPOINT_1MM_SQUARE"))
    )
    (comp (ref "TP21")
      (value "TESTPOINT_1MM_SQUARE")
      (footprint "TESTPOINT_SQUARE_1MM")
      (description "TESTPOINT 1MM SQUARE")
      (libsource (lib "Personal_Schematic_Library_2022") (part "TESTPOINT_1MM_SQUARE"))
    )
    (comp (ref "TP22")
      (value "TESTPOINT_1MM_SQUARE")
      (footprint "TESTPOINT_SQUARE_1MM")
      (description "TESTPOINT 1MM SQUARE")
      (libsource (lib "Personal_Schematic_Library_2022") (part "TESTPOINT_1MM_SQUARE"))
    )
    (comp (ref "TP23")
      (value "TESTPOINT_1MM_SQUARE")
      (footprint "TESTPOINT_SQUARE_1MM")
      (description "TESTPOINT 1MM SQUARE")
      (libsource (lib "Personal_Schematic_Library_2022") (part "TESTPOINT_1MM_SQUARE"))
    )
    (comp (ref "TP24")
      (value "TESTPOINT_1MM_SQUARE")
      (footprint "TESTPOINT_SQUARE_1MM")
      (description "TESTPOINT 1MM SQUARE")
      (libsource (lib "Personal_Schematic_Library_2022") (part "TESTPOINT_1MM_SQUARE"))
    )
    (comp (ref "TP25")
      (value "TESTPOINT_1MM_SQUARE")
      (footprint "TESTPOINT_SQUARE_1MM")
      (description "TESTPOINT 1MM SQUARE")
      (libsource (lib "Personal_Schematic_Library_2022") (part "TESTPOINT_1MM_SQUARE"))
    )
    (comp (ref "TP26")
      (value "TESTPOINT_1MM_SQUARE")
      (footprint "TESTPOINT_SQUARE_1MM")
      (description "TESTPOINT 1MM SQUARE")
      (libsource (lib "Personal_Schematic_Library_2022") (part "TESTPOINT_1MM_SQUARE"))
    )
    (comp (ref "TP27")
      (value "TESTPOINT_1MM_SQUARE")
      (footprint "TESTPOINT_SQUARE_1MM")
      (description "TESTPOINT 1MM SQUARE")
      (libsource (lib "Personal_Schematic_Library_2022") (part "TESTPOINT_1MM_SQUARE"))
    )
    (comp (ref "TP28")
      (value "TESTPOINT_1MM_SQUARE")
      (footprint "TESTPOINT_SQUARE_1MM")
      (description "TESTPOINT 1MM SQUARE")
      (libsource (lib "Personal_Schematic_Library_2022") (part "TESTPOINT_1MM_SQUARE"))
    )
    (comp (ref "TP29")
      (value "TESTPOINT_1MM_SQUARE")
      (footprint "TESTPOINT_SQUARE_1MM")
      (description "TESTPOINT 1MM SQUARE")
      (libsource (lib "Personal_Schematic_Library_2022") (part "TESTPOINT_1MM_SQUARE"))
    )
    (comp (ref "TP30")
      (value "TESTPOINT_1MM_SQUARE")
      (footprint "TESTPOINT_SQUARE_1MM")
      (description "TESTPOINT 1MM SQUARE")
      (libsource (lib "Personal_Schematic_Library_2022") (part "TESTPOINT_1MM_SQUARE"))
    )
    (comp (ref "TP31")
      (value "TESTPOINT_1MM_SQUARE")
      (footprint "TESTPOINT_SQUARE_1MM")
      (description "TESTPOINT 1MM SQUARE")
      (libsource (lib "Personal_Schematic_Library_2022") (part "TESTPOINT_1MM_SQUARE"))
    )
    (comp (ref "TP32")
      (value "TESTPOINT_1MM_SQUARE")
      (footprint "TESTPOINT_SQUARE_1MM")
      (description "TESTPOINT 1MM SQUARE")
      (libsource (lib "Personal_Schematic_Library_2022") (part "TESTPOINT_1MM_SQUARE"))
    )
    (comp (ref "TP33")
      (value "TESTPOINT_1MM_SQUARE")
      (footprint "TESTPOINT_SQUARE_1MM")
      (description "TESTPOINT 1MM SQUARE")
      (libsource (lib "Personal_Schematic_Library_2022") (part "TESTPOINT_1MM_SQUARE"))
    )
    (comp (ref "TP34")
      (value "TESTPOINT_1MM_SQUARE")
      (footprint "TESTPOINT_SQUARE_1MM")
      (description "TESTPOINT 1MM SQUARE")
      (libsource (lib "Personal_Schematic_Library_2022") (part "TESTPOINT_1MM_SQUARE"))
    )
    (comp (ref "TP35")
      (value "TESTPOINT_1MM_SQUARE")
      (footprint "TESTPOINT_SQUARE_1MM")
      (description "TESTPOINT 1MM SQUARE")
      (libsource (lib "Personal_Schematic_Library_2022") (part "TESTPOINT_1MM_SQUARE"))
    )
    (comp (ref "TP36")
      (value "TESTPOINT_1MM_SQUARE")
      (footprint "TESTPOINT_SQUARE_1MM")
      (description "TESTPOINT 1MM SQUARE")
      (libsource (lib "Personal_Schematic_Library_2022") (part "TESTPOINT_1MM_SQUARE"))
    )
    (comp (ref "TP37")
      (value "TESTPOINT_1MM_SQUARE")
      (footprint "TESTPOINT_SQUARE_1MM")
      (description "TESTPOINT 1MM SQUARE")
      (libsource (lib "Personal_Schematic_Library_2022") (part "TESTPOINT_1MM_SQUARE"))
    )
    (comp (ref "TP38")
      (value "TESTPOINT_1MM_SQUARE")
      (footprint "TESTPOINT_SQUARE_1MM")
      (description "TESTPOINT 1MM SQUARE")
      (libsource (lib "Personal_Schematic_Library_2022") (part "TESTPOINT_1MM_SQUARE"))
    )
  )
  (nets
    (net (code "1") (name "/CELL_V0") (class "Default")
      (node (ref "D1") (pin "1") (pinfunction "Anode_1") (pintype "passive"))
      (node (ref "Q1") (pin "2") (pinfunction "SOURCE_2") (pintype "passive"))
      (node (ref "R1") (pin "1") (pinfunction "1_1") (pintype "passive"))
      (node (ref "TP21") (pin "1") (pinfunction "=value_1") (pintype "passive"))
    )
    (net (code "2") (name "/CELL_V1") (class "Default")
      (node (ref "D2") (pin "1") (pinfunction "Anode_1") (pintype "passive"))
      (node (ref "Q2") (pin "2") (pinfunction "SOURCE_2") (pintype "passive"))
      (node (ref "R2") (pin "1") (pinfunction "1_1") (pintype "passive"))
      (node (ref "R34") (pin "2") (pinfunction "2_2") (pintype "passive"))
      (node (ref "TP20") (pin "1") (pinfunction "=value_1") (pintype "passive"))
    )
    (net (code "3") (name "/CELL_V2") (class "Default")
      (node (ref "D3") (pin "1") (pinfunction "Anode_1") (pintype "passive"))
      (node (ref "Q3") (pin "2") (pinfunction "SOURCE_2") (pintype "passive"))
      (node (ref "R3") (pin "1") (pinfunction "1_1") (pintype "passive"))
      (node (ref "R35") (pin "2") (pinfunction "2_2") (pintype "passive"))
      (node (ref "TP19") (pin "1") (pinfunction "=value_1") (pintype "passive"))
    )
    (net (code "4") (name "/CELL_V3") (class "Default")
      (node (ref "D4") (pin "1") (pinfunction "Anode_1") (pintype "passive"))
      (node (ref "Q4") (pin "2") (pinfunction "SOURCE_2") (pintype "passive"))
      (node (ref "R36") (pin "2") (pinfunction "2_2") (pintype "passive"))
      (node (ref "R4") (pin "1") (pinfunction "1_1") (pintype "passive"))
      (node (ref "TP18") (pin "1") (pinfunction "=value_1") (pintype "passive"))
    )
    (net (code "5") (name "/CELL_V4") (class "Default")
      (node (ref "D5") (pin "1") (pinfunction "Anode_1") (pintype "passive"))
      (node (ref "Q5") (pin "2") (pinfunction "SOURCE_2") (pintype "passive"))
      (node (ref "R37") (pin "2") (pinfunction "2_2") (pintype "passive"))
      (node (ref "R5") (pin "1") (pinfunction "1_1") (pintype "passive"))
      (node (ref "TP17") (pin "1") (pinfunction "=value_1") (pintype "passive"))
    )
    (net (code "6") (name "/CELL_V5") (class "Default")
      (node (ref "D6") (pin "1") (pinfunction "Anode_1") (pintype "passive"))
      (node (ref "Q6") (pin "2") (pinfunction "SOURCE_2") (pintype "passive"))
      (node (ref "R38") (pin "2") (pinfunction "2_2") (pintype "passive"))
      (node (ref "R6") (pin "1") (pinfunction "1_1") (pintype "passive"))
      (node (ref "TP15") (pin "1") (pinfunction "=value_1") (pintype "passive"))
    )
    (net (code "7") (name "/CELL_V6") (class "Default")
      (node (ref "D7") (pin "1") (pinfunction "Anode_1") (pintype "passive"))
      (node (ref "Q7") (pin "2") (pinfunction "SOURCE_2") (pintype "passive"))
      (node (ref "R39") (pin "2") (pinfunction "2_2") (pintype "passive"))
      (node (ref "R7") (pin "1") (pinfunction "1_1") (pintype "passive"))
      (node (ref "TP14") (pin "1") (pinfunction "=value_1") (pintype "passive"))
    )
    (net (code "8") (name "/CELL_V7") (class "Default")
      (node (ref "D8") (pin "1") (pinfunction "Anode_1") (pintype "passive"))
      (node (ref "Q8") (pin "2") (pinfunction "SOURCE_2") (pintype "passive"))
      (node (ref "R40") (pin "2") (pinfunction "2_2") (pintype "passive"))
      (node (ref "R8") (pin "1") (pinfunction "1_1") (pintype "passive"))
      (node (ref "TP13") (pin "1") (pinfunction "=value_1") (pintype "passive"))
    )
    (net (code "9") (name "/CELL_V8") (class "Default")
      (node (ref "D9") (pin "1") (pinfunction "Anode_1") (pintype "passive"))
      (node (ref "Q9") (pin "2") (pinfunction "SOURCE_2") (pintype "passive"))
      (node (ref "R41") (pin "2") (pinfunction "2_2") (pintype "passive"))
      (node (ref "R9") (pin "1") (pinfunction "1_1") (pintype "passive"))
      (node (ref "TP12") (pin "1") (pinfunction "=value_1") (pintype "passive"))
    )
    (net (code "10") (name "/CELL_V9") (class "Default")
      (node (ref "D10") (pin "1") (pinfunction "Anode_1") (pintype "passive"))
      (node (ref "Q10") (pin "2") (pinfunction "SOURCE_2") (pintype "passive"))
      (node (ref "R10") (pin "1") (pinfunction "1_1") (pintype "passive"))
      (node (ref "R42") (pin "2") (pinfunction "2_2") (pintype "passive"))
      (node (ref "TP11") (pin "1") (pinfunction "=value_1") (pintype "passive"))
    )
    (net (code "11") (name "/CELL_V10") (class "Default")
      (node (ref "D11") (pin "1") (pinfunction "Anode_1") (pintype "passive"))
      (node (ref "Q11") (pin "2") (pinfunction "SOURCE_2") (pintype "passive"))
      (node (ref "R11") (pin "1") (pinfunction "1_1") (pintype "passive"))
      (node (ref "R43") (pin "2") (pinfunction "2_2") (pintype "passive"))
      (node (ref "TP10") (pin "1") (pinfunction "=value_1") (pintype "passive"))
    )
    (net (code "12") (name "/CELL_V11") (class "Default")
      (node (ref "D12") (pin "1") (pinfunction "Anode_1") (pintype "passive"))
      (node (ref "Q12") (pin "2") (pinfunction "SOURCE_2") (pintype "passive"))
      (node (ref "R12") (pin "1") (pinfunction "1_1") (pintype "passive"))
      (node (ref "R44") (pin "2") (pinfunction "2_2") (pintype "passive"))
      (node (ref "TP9") (pin "1") (pinfunction "=value_1") (pintype "passive"))
    )
    (net (code "13") (name "/CELL_V12") (class "Default")
      (node (ref "D13") (pin "1") (pinfunction "Anode_1") (pintype "passive"))
      (node (ref "Q13") (pin "2") (pinfunction "SOURCE_2") (pintype "passive"))
      (node (ref "R13") (pin "1") (pinfunction "1_1") (pintype "passive"))
      (node (ref "R45") (pin "2") (pinfunction "2_2") (pintype "passive"))
      (node (ref "TP8") (pin "1") (pinfunction "=value_1") (pintype "passive"))
    )
    (net (code "14") (name "/CELL_V13") (class "Default")
      (node (ref "D14") (pin "1") (pinfunction "Anode_1") (pintype "passive"))
      (node (ref "Q14") (pin "2") (pinfunction "SOURCE_2") (pintype "passive"))
      (node (ref "R14") (pin "1") (pinfunction "1_1") (pintype "passive"))
      (node (ref "R46") (pin "2") (pinfunction "2_2") (pintype "passive"))
      (node (ref "TP7") (pin "1") (pinfunction "=value_1") (pintype "passive"))
    )
    (net (code "15") (name "/CELL_V14") (class "Default")
      (node (ref "D15") (pin "1") (pinfunction "Anode_1") (pintype "passive"))
      (node (ref "Q15") (pin "2") (pinfunction "SOURCE_2") (pintype "passive"))
      (node (ref "R15") (pin "1") (pinfunction "1_1") (pintype "passive"))
      (node (ref "R47") (pin "2") (pinfunction "2_2") (pintype "passive"))
      (node (ref "TP6") (pin "1") (pinfunction "=value_1") (pintype "passive"))
    )
    (net (code "16") (name "/CELL_V15") (class "Default")
      (node (ref "D16") (pin "1") (pinfunction "Anode_1") (pintype "passive"))
      (node (ref "Q16") (pin "2") (pinfunction "SOURCE_2") (pintype "passive"))
      (node (ref "R16") (pin "1") (pinfunction "1_1") (pintype "passive"))
      (node (ref "R48") (pin "2") (pinfunction "2_2") (pintype "passive"))
      (node (ref "TP5") (pin "1") (pinfunction "=value_1") (pintype "passive"))
    )
    (net (code "17") (name "/CELL_V16") (class "Default")
      (node (ref "R17") (pin "1") (pinfunction "1_1") (pintype "passive"))
      (node (ref "R49") (pin "2") (pinfunction "2_2") (pintype "passive"))
      (node (ref "TP4") (pin "1") (pinfunction "=value_1") (pintype "passive"))
    )
    (net (code "19") (name "/VC0") (class "Default")
      (node (ref "C1") (pin "2") (pinfunction "2_2") (pintype "passive"))
      (node (ref "R1") (pin "2") (pinfunction "2_2") (pintype "passive"))
      (node (ref "R18") (pin "2") (pinfunction "2_2") (pintype "passive"))
      (node (ref "TP38") (pin "1") (pinfunction "=value_1") (pintype "passive"))
    )
    (net (code "20") (name "/VC1") (class "Default")
      (node (ref "C2") (pin "2") (pinfunction "2_2") (pintype "passive"))
      (node (ref "C3") (pin "1") (pinfunction "1_1") (pintype "passive"))
      (node (ref "R19") (pin "2") (pinfunction "2_2") (pintype "passive"))
      (node (ref "R2") (pin "2") (pinfunction "2_2") (pintype "passive"))
      (node (ref "TP37") (pin "1") (pinfunction "=value_1") (pintype "passive"))
    )
    (net (code "21") (name "/VC2") (class "Default")
      (node (ref "C3") (pin "2") (pinfunction "2_2") (pintype "passive"))
      (node (ref "C4") (pin "1") (pinfunction "1_1") (pintype "passive"))
      (node (ref "R20") (pin "2") (pinfunction "2_2") (pintype "passive"))
      (node (ref "R3") (pin "2") (pinfunction "2_2") (pintype "passive"))
      (node (ref "TP36") (pin "1") (pinfunction "=value_1") (pintype "passive"))
    )
    (net (code "22") (name "/VC3") (class "Default")
      (node (ref "C4") (pin "2") (pinfunction "2_2") (pintype "passive"))
      (node (ref "C5") (pin "1") (pinfunction "1_1") (pintype "passive"))
      (node (ref "R21") (pin "2") (pinfunction "2_2") (pintype "passive"))
      (node (ref "R4") (pin "2") (pinfunction "2_2") (pintype "passive"))
      (node (ref "TP35") (pin "1") (pinfunction "=value_1") (pintype "passive"))
    )
    (net (code "23") (name "/VC4") (class "Default")
      (node (ref "C5") (pin "2") (pinfunction "2_2") (pintype "passive"))
      (node (ref "C6") (pin "1") (pinfunction "1_1") (pintype "passive"))
      (node (ref "R22") (pin "2") (pinfunction "2_2") (pintype "passive"))
      (node (ref "R5") (pin "2") (pinfunction "2_2") (pintype "passive"))
      (node (ref "TP34") (pin "1") (pinfunction "=value_1") (pintype "passive"))
    )
    (net (code "24") (name "/VC5") (class "Default")
      (node (ref "C6") (pin "2") (pinfunction "2_2") (pintype "passive"))
      (node (ref "C7") (pin "1") (pinfunction "1_1") (pintype "passive"))
      (node (ref "R23") (pin "2") (pinfunction "2_2") (pintype "passive"))
      (node (ref "R6") (pin "2") (pinfunction "2_2") (pintype "passive"))
      (node (ref "TP33") (pin "1") (pinfunction "=value_1") (pintype "passive"))
    )
    (net (code "25") (name "/VC6") (class "Default")
      (node (ref "C7") (pin "2") (pinfunction "2_2") (pintype "passive"))
      (node (ref "C8") (pin "1") (pinfunction "1_1") (pintype "passive"))
      (node (ref "R24") (pin "2") (pinfunction "2_2") (pintype "passive"))
      (node (ref "R7") (pin "2") (pinfunction "2_2") (pintype "passive"))
      (node (ref "TP32") (pin "1") (pinfunction "=value_1") (pintype "passive"))
    )
    (net (code "26") (name "/VC7") (class "Default")
      (node (ref "C8") (pin "2") (pinfunction "2_2") (pintype "passive"))
      (node (ref "C9") (pin "1") (pinfunction "1_1") (pintype "passive"))
      (node (ref "R25") (pin "2") (pinfunction "2_2") (pintype "passive"))
      (node (ref "R8") (pin "2") (pinfunction "2_2") (pintype "passive"))
      (node (ref "TP31") (pin "1") (pinfunction "=value_1") (pintype "passive"))
    )
    (net (code "27") (name "/VC8") (class "Default")
      (node (ref "C10") (pin "1") (pinfunction "1_1") (pintype "passive"))
      (node (ref "C9") (pin "2") (pinfunction "2_2") (pintype "passive"))
      (node (ref "R26") (pin "2") (pinfunction "2_2") (pintype "passive"))
      (node (ref "R9") (pin "2") (pinfunction "2_2") (pintype "passive"))
      (node (ref "TP30") (pin "1") (pinfunction "=value_1") (pintype "passive"))
    )
    (net (code "28") (name "/VC9") (class "Default")
      (node (ref "C10") (pin "2") (pinfunction "2_2") (pintype "passive"))
      (node (ref "C11") (pin "1") (pinfunction "1_1") (pintype "passive"))
      (node (ref "R10") (pin "2") (pinfunction "2_2") (pintype "passive"))
      (node (ref "R27") (pin "2") (pinfunction "2_2") (pintype "passive"))
      (node (ref "TP29") (pin "1") (pinfunction "=value_1") (pintype "passive"))
    )
    (net (code "29") (name "/VC10") (class "Default")
      (node (ref "C11") (pin "2") (pinfunction "2_2") (pintype "passive"))
      (node (ref "C12") (pin "1") (pinfunction "1_1") (pintype "passive"))
      (node (ref "R11") (pin "2") (pinfunction "2_2") (pintype "passive"))
      (node (ref "R28") (pin "2") (pinfunction "2_2") (pintype "passive"))
      (node (ref "TP28") (pin "1") (pinfunction "=value_1") (pintype "passive"))
    )
    (net (code "30") (name "/VC11") (class "Default")
      (node (ref "C12") (pin "2") (pinfunction "2_2") (pintype "passive"))
      (node (ref "C13") (pin "1") (pinfunction "1_1") (pintype "passive"))
      (node (ref "R12") (pin "2") (pinfunction "2_2") (pintype "passive"))
      (node (ref "R29") (pin "2") (pinfunction "2_2") (pintype "passive"))
      (node (ref "TP27") (pin "1") (pinfunction "=value_1") (pintype "passive"))
    )
    (net (code "31") (name "/VC12") (class "Default")
      (node (ref "C13") (pin "2") (pinfunction "2_2") (pintype "passive"))
      (node (ref "C14") (pin "1") (pinfunction "1_1") (pintype "passive"))
      (node (ref "R13") (pin "2") (pinfunction "2_2") (pintype "passive"))
      (node (ref "R30") (pin "2") (pinfunction "2_2") (pintype "passive"))
      (node (ref "TP26") (pin "1") (pinfunction "=value_1") (pintype "passive"))
    )
    (net (code "32") (name "/VC13") (class "Default")
      (node (ref "C14") (pin "2") (pinfunction "2_2") (pintype "passive"))
      (node (ref "C15") (pin "1") (pinfunction "1_1") (pintype "passive"))
      (node (ref "R14") (pin "2") (pinfunction "2_2") (pintype "passive"))
      (node (ref "R31") (pin "2") (pinfunction "2_2") (pintype "passive"))
      (node (ref "TP25") (pin "1") (pinfunction "=value_1") (pintype "passive"))
    )
    (net (code "33") (name "/VC14") (class "Default")
      (node (ref "C15") (pin "2") (pinfunction "2_2") (pintype "passive"))
      (node (ref "C16") (pin "1") (pinfunction "1_1") (pintype "passive"))
      (node (ref "R15") (pin "2") (pinfunction "2_2") (pintype "passive"))
      (node (ref "R32") (pin "2") (pinfunction "2_2") (pintype "passive"))
      (node (ref "TP24") (pin "1") (pinfunction "=value_1") (pintype "passive"))
    )
    (net (code "34") (name "/VC15") (class "Default")
      (node (ref "C16") (pin "2") (pinfunction "2_2") (pintype "passive"))
      (node (ref "C17") (pin "1") (pinfunction "1_1") (pintype "passive"))
      (node (ref "R16") (pin "2") (pinfunction "2_2") (pintype "passive"))
      (node (ref "R33") (pin "2") (pinfunction "2_2") (pintype "passive"))
      (node (ref "TP23") (pin "1") (pinfunction "=value_1") (pintype "passive"))
    )
    (net (code "35") (name "/VC16") (class "Default")
      (node (ref "C17") (pin "2") (pinfunction "2_2") (pintype "passive"))
      (node (ref "R17") (pin "2") (pinfunction "2_2") (pintype "passive"))
      (node (ref "TP22") (pin "1") (pinfunction "=value_1") (pintype "passive"))
    )
    (net (code "37") (name "Net-(D1-Cathode)") (class "Default")
      (node (ref "D1") (pin "2") (pinfunction "Cathode_2") (pintype "passive"))
      (node (ref "Q1") (pin "1") (pinfunction "GATE_1") (pintype "passive"))
      (node (ref "R18") (pin "1") (pinfunction "1_1") (pintype "passive"))
    )
    (net (code "38") (name "Net-(D2-Cathode)") (class "Default")
      (node (ref "D2") (pin "2") (pinfunction "Cathode_2") (pintype "passive"))
      (node (ref "Q2") (pin "1") (pinfunction "GATE_1") (pintype "passive"))
      (node (ref "R19") (pin "1") (pinfunction "1_1") (pintype "passive"))
    )
    (net (code "39") (name "Net-(D3-Cathode)") (class "Default")
      (node (ref "D3") (pin "2") (pinfunction "Cathode_2") (pintype "passive"))
      (node (ref "Q3") (pin "1") (pinfunction "GATE_1") (pintype "passive"))
      (node (ref "R20") (pin "1") (pinfunction "1_1") (pintype "passive"))
    )
    (net (code "40") (name "Net-(D4-Cathode)") (class "Default")
      (node (ref "D4") (pin "2") (pinfunction "Cathode_2") (pintype "passive"))
      (node (ref "Q4") (pin "1") (pinfunction "GATE_1") (pintype "passive"))
      (node (ref "R21") (pin "1") (pinfunction "1_1") (pintype "passive"))
    )
    (net (code "41") (name "Net-(D5-Cathode)") (class "Default")
      (node (ref "D5") (pin "2") (pinfunction "Cathode_2") (pintype "passive"))
      (node (ref "Q5") (pin "1") (pinfunction "GATE_1") (pintype "passive"))
      (node (ref "R22") (pin "1") (pinfunction "1_1") (pintype "passive"))
    )
    (net (code "42") (name "Net-(D6-Cathode)") (class "Default")
      (node (ref "D6") (pin "2") (pinfunction "Cathode_2") (pintype "passive"))
      (node (ref "Q6") (pin "1") (pinfunction "GATE_1") (pintype "passive"))
      (node (ref "R23") (pin "1") (pinfunction "1_1") (pintype "passive"))
    )
    (net (code "43") (name "Net-(D7-Cathode)") (class "Default")
      (node (ref "D7") (pin "2") (pinfunction "Cathode_2") (pintype "passive"))
      (node (ref "Q7") (pin "1") (pinfunction "GATE_1") (pintype "passive"))
      (node (ref "R24") (pin "1") (pinfunction "1_1") (pintype "passive"))
    )
    (net (code "44") (name "Net-(D8-Cathode)") (class "Default")
      (node (ref "D8") (pin "2") (pinfunction "Cathode_2") (pintype "passive"))
      (node (ref "Q8") (pin "1") (pinfunction "GATE_1") (pintype "passive"))
      (node (ref "R25") (pin "1") (pinfunction "1_1") (pintype "passive"))
    )
    (net (code "45") (name "Net-(D9-Cathode)") (class "Default")
      (node (ref "D9") (pin "2") (pinfunction "Cathode_2") (pintype "passive"))
      (node (ref "Q9") (pin "1") (pinfunction "GATE_1") (pintype "passive"))
      (node (ref "R26") (pin "1") (pinfunction "1_1") (pintype "passive"))
    )
    (net (code "46") (name "Net-(D10-Cathode)") (class "Default")
      (node (ref "D10") (pin "2") (pinfunction "Cathode_2") (pintype "passive"))
      (node (ref "Q10") (pin "1") (pinfunction "GATE_1") (pintype "passive"))
      (node (ref "R27") (pin "1") (pinfunction "1_1") (pintype "passive"))
    )
    (net (code "47") (name "Net-(D11-Cathode)") (class "Default")
      (node (ref "D11") (pin "2") (pinfunction "Cathode_2") (pintype "passive"))
      (node (ref "Q11") (pin "1") (pinfunction "GATE_1") (pintype "passive"))
      (node (ref "R28") (pin "1") (pinfunction "1_1") (pintype "passive"))
    )
    (net (code "48") (name "Net-(D12-Cathode)") (class "Default")
      (node (ref "D12") (pin "2") (pinfunction "Cathode_2") (pintype "passive"))
      (node (ref "Q12") (pin "1") (pinfunction "GATE_1") (pintype "passive"))
      (node (ref "R29") (pin "1") (pinfunction "1_1") (pintype "passive"))
    )
    (net (code "49") (name "Net-(D13-Cathode)") (class "Default")
      (node (ref "D13") (pin "2") (pinfunction "Cathode_2") (pintype "passive"))
      (node (ref "Q13") (pin "1") (pinfunction "GATE_1") (pintype "passive"))
      (node (ref "R30") (pin "1") (pinfunction "1_1") (pintype "passive"))
    )
    (net (code "50") (name "Net-(D14-Cathode)") (class "Default")
      (node (ref "D14") (pin "2") (pinfunction "Cathode_2") (pintype "passive"))
      (node (ref "Q14") (pin "1") (pinfunction "GATE_1") (pintype "passive"))
      (node (ref "R31") (pin "1") (pinfunction "1_1") (pintype "passive"))
    )
    (net (code "51") (name "Net-(D15-Cathode)") (class "Default")
      (node (ref "D15") (pin "2") (pinfunction "Cathode_2") (pintype "passive"))
      (node (ref "Q15") (pin "1") (pinfunction "GATE_1") (pintype "passive"))
      (node (ref "R32") (pin "1") (pinfunction "1_1") (pintype "passive"))
    )
    (net (code "52") (name "Net-(D16-Cathode)") (class "Default")
      (node (ref "D16") (pin "2") (pinfunction "Cathode_2") (pintype "passive"))
      (node (ref "Q16") (pin "1") (pinfunction "GATE_1") (pintype "passive"))
      (node (ref "R33") (pin "1") (pinfunction "1_1") (pintype "passive"))
    )
    (net (code "53") (name "Net-(Q1-DRAIN)") (class "Default")
      (node (ref "Q1") (pin "3") (pinfunction "DRAIN_3") (pintype "passive"))
      (node (ref "R34") (pin "1") (pinfunction "1_1") (pintype "passive"))
    )
    (net (code "54") (name "Net-(Q2-DRAIN)") (class "Default")
      (node (ref "Q2") (pin "3") (pinfunction "DRAIN_3") (pintype "passive"))
      (node (ref "R35") (pin "1") (pinfunction "1_1") (pintype "passive"))
    )
    (net (code "55") (name "Net-(Q3-DRAIN)") (class "Default")
      (node (ref "Q3") (pin "3") (pinfunction "DRAIN_3") (pintype "passive"))
      (node (ref "R36") (pin "1") (pinfunction "1_1") (pintype "passive"))
    )
    (net (code "56") (name "Net-(Q4-DRAIN)") (class "Default")
      (node (ref "Q4") (pin "3") (pinfunction "DRAIN_3") (pintype "passive"))
      (node (ref "R37") (pin "1") (pinfunction "1_1") (pintype "passive"))
    )
    (net (code "57") (name "Net-(Q5-DRAIN)") (class "Default")
      (node (ref "Q5") (pin "3") (pinfunction "DRAIN_3") (pintype "passive"))
      (node (ref "R38") (pin "1") (pinfunction "1_1") (pintype "passive"))
    )
    (net (code "58") (name "Net-(Q6-DRAIN)") (class "Default")
      (node (ref "Q6") (pin "3") (pinfunction "DRAIN_3") (pintype "passive"))
      (node (ref "R39") (pin "1") (pinfunction "1_1") (pintype "passive"))
    )
    (net (code "59") (name "Net-(Q7-DRAIN)") (class "Default")
      (node (ref "Q7") (pin "3") (pinfunction "DRAIN_3") (pintype "passive"))
      (node (ref "R40") (pin "1") (pinfunction "1_1") (pintype "passive"))
    )
    (net (code "60") (name "Net-(Q8-DRAIN)") (class "Default")
      (node (ref "Q8") (pin "3") (pinfunction "DRAIN_3") (pintype "passive"))
      (node (ref "R41") (pin "1") (pinfunction "1_1") (pintype "passive"))
    )
    (net (code "61") (name "Net-(Q9-DRAIN)") (class "Default")
      (node (ref "Q9") (pin "3") (pinfunction "DRAIN_3") (pintype "passive"))
      (node (ref "R42") (pin "1") (pinfunction "1_1") (pintype "passive"))
    )
    (net (code "62") (name "Net-(Q10-DRAIN)") (class "Default")
      (node (ref "Q10") (pin "3") (pinfunction "DRAIN_3") (pintype "passive"))
      (node (ref "R43") (pin "1") (pinfunction "1_1") (pintype "passive"))
    )
    (net (code "63") (name "Net-(Q11-DRAIN)") (class "Default")
      (node (ref "Q11") (pin "3") (pinfunction "DRAIN_3") (pintype "passive"))
      (node (ref "R44") (pin "1") (pinfunction "1_1") (pintype "passive"))
    )
    (net (code "64") (name "Net-(Q12-DRAIN)") (class "Default")
      (node (ref "Q12") (pin "3") (pinfunction "DRAIN_3") (pintype "passive"))
      (node (ref "R45") (pin "1") (pinfunction "1_1") (pintype "passive"))
    )
    (net (code "65") (name "Net-(Q13-DRAIN)") (class "Default")
      (node (ref "Q13") (pin "3") (pinfunction "DRAIN_3") (pintype "passive"))
      (node (ref "R46") (pin "1") (pinfunction "1_1") (pintype "passive"))
    )
    (net (code "66") (name "Net-(Q14-DRAIN)") (class "Default")
      (node (ref "Q14") (pin "3") (pinfunction "DRAIN_3") (pintype "passive"))
      (node (ref "R47") (pin "1") (pinfunction "1_1") (pintype "passive"))
    )
    (net (code "67") (name "Net-(Q15-DRAIN)") (class "Default")
      (node (ref "Q15") (pin "3") (pinfunction "DRAIN_3") (pintype "passive"))
      (node (ref "R48") (pin "1") (pinfunction "1_1") (pintype "passive"))
    )
    (net (code "68") (name "Net-(Q16-DRAIN)") (class "Default")
      (node (ref "Q16") (pin "3") (pinfunction "DRAIN_3") (pintype "passive"))
      (node (ref "R49") (pin "1") (pinfunction "1_1") (pintype "passive"))
    )
    (net (code "69") (name "VBAT-") (class "Default")
      (node (ref "C1") (pin "1") (pinfunction "1_1") (pintype "passive"))
      (node (ref "C2") (pin "1") (pinfunction "1_1") (pintype "passive"))
    )
  )
)
